# PCBRecSCH.net
KiCad netlist of a schematic drawn in Altium Designer
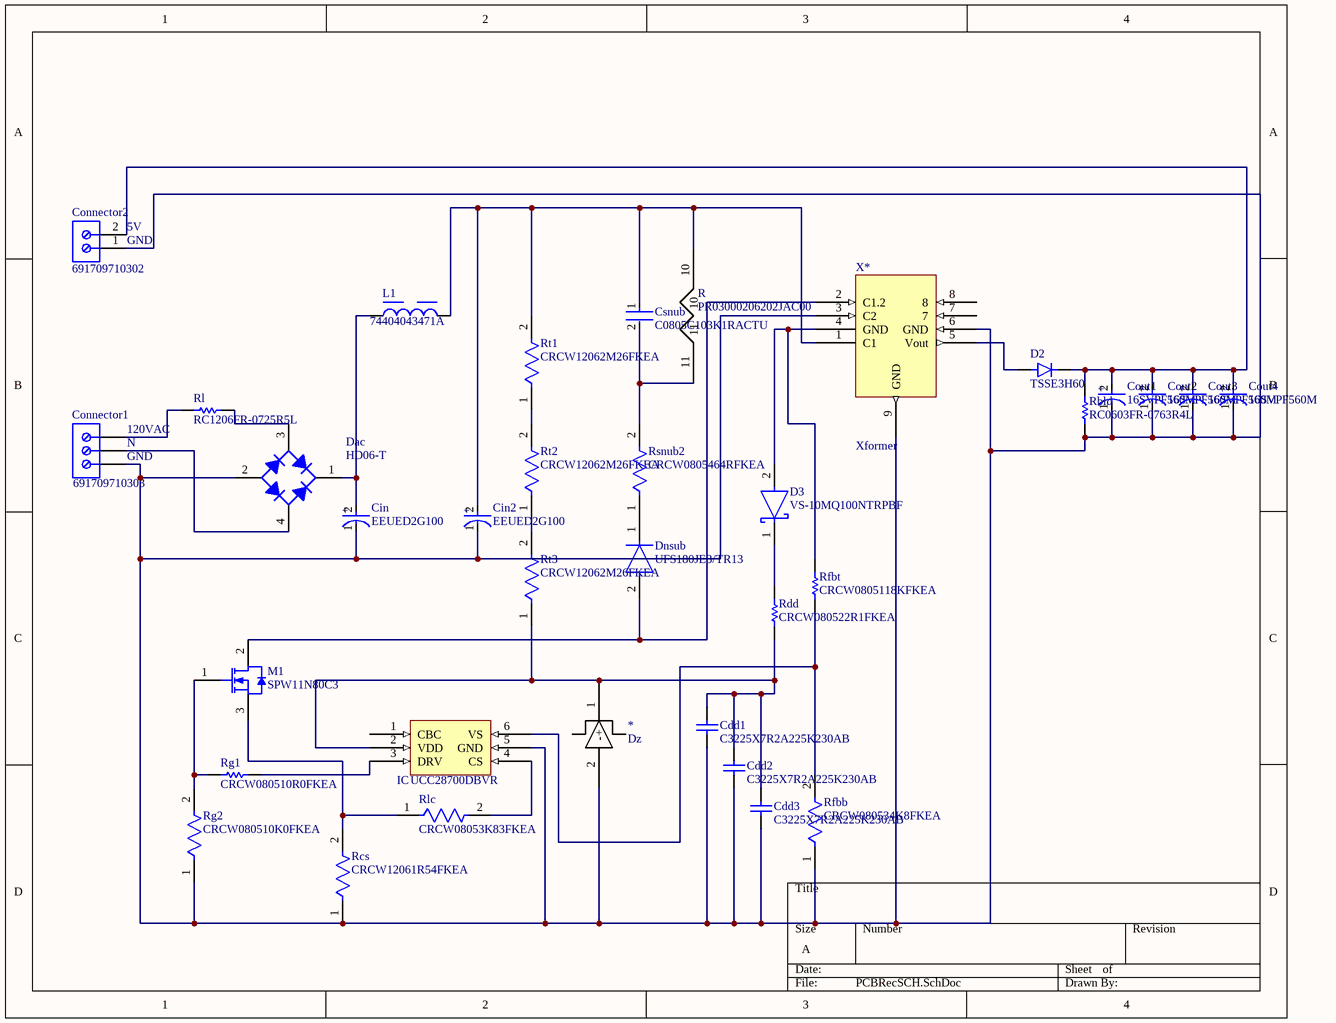
[diagram p0: PCBRecSCH.SchDoc]

(export (version "E")
  (design (tool "Eeschema 10.0.6"))
  (components
    (comp (ref "*")
      (value "Dz")
      (footprint "DIOM505270X240")
      (libsource (lib "Integrated_Library2") (part "Component_1"))
    )
    (comp (ref "Cdd1")
      (value "C3225X7R2A225K230AB")
      (footprint "CAPC3225X250X20LL40")
      (description "Chip Capacitor, 2.2 uF, +/- 10%, -55 to 125 degC, 1210 (3225 Metric), RoHS, Tape and Reel")
      (fields
        (field (name "PCN PART NUMBER") "MLCCPartNumberChange30/Nov/2012")
        (field (name "MANUFACTURER") "TDK")
      )
      (libsource (lib "Altium Content Vault") (part "CAP-NP-2"))
    )
    (comp (ref "Cdd2")
      (value "C3225X7R2A225K230AB")
      (footprint "CAPC3225X250X20LL40")
      (description "Chip Capacitor, 2.2 uF, +/- 10%, -55 to 125 degC, 1210 (3225 Metric), RoHS, Tape and Reel")
      (fields
        (field (name "PCN PART NUMBER") "MLCCPartNumberChange30/Nov/2012")
        (field (name "MANUFACTURER") "TDK")
      )
      (libsource (lib "Altium Content Vault") (part "CAP-NP-2"))
    )
    (comp (ref "Cdd3")
      (value "C3225X7R2A225K230AB")
      (footprint "CAPC3225X250X20LL40")
      (description "Chip Capacitor, 2.2 uF, +/- 10%, -55 to 125 degC, 1210 (3225 Metric), RoHS, Tape and Reel")
      (fields
        (field (name "PCN PART NUMBER") "MLCCPartNumberChange30/Nov/2012")
        (field (name "MANUFACTURER") "TDK")
      )
      (libsource (lib "Altium Content Vault") (part "CAP-NP-2"))
    )
    (comp (ref "Cin")
      (value "EEUED2G100")
      (footprint "FP-RAD-TH-D_10_0_5-L_20_2-MFG")
      (description "Aluminum Electrolytic Capacitors (Radial Lead Type) 10uF ±20% 400V")
      (fields (field (name "VOLTAGE") "400V") (field (name "TOLERANCE") "20%"))
      (libsource (lib "Altium Content Vault") (part "203bc49f2ac43e59fd269a8c329ed05"))
    )
    (comp (ref "Cin2")
      (value "EEUED2G100")
      (footprint "FP-RAD-TH-D_10_0_5-L_20_2-MFG")
      (description "Aluminum Electrolytic Capacitors (Radial Lead Type) 10uF ±20% 400V")
      (fields (field (name "VOLTAGE") "400V") (field (name "TOLERANCE") "20%"))
      (libsource (lib "Altium Content Vault") (part "203bc49f2ac43e59fd269a8c329ed05"))
    )
    (comp (ref "Connector1")
      (value "691709710303")
      (footprint "691709710303")
      (fields (field (name "VOLTAGE") "300V"))
      (libsource (lib "Altium Content Vault") (part "TBL - 1R - 03P - Screw"))
    )
    (comp (ref "Connector2")
      (value "691709710302")
      (footprint "691709710302")
      (fields (field (name "VOLTAGE") "300V"))
      (libsource (lib "Altium Content Vault") (part "TBL - 1R - 02P - Screw"))
    )
    (comp (ref "Cout1")
      (value "16SVPF560M")
      (footprint "FP-OS-CON-SMT-E12-MFG")
      (description "Conductive Polymer Aluminum Solid Capacitors (OS-CON) 560uF ±20% 16V")
      (fields (field (name "TOLERANCE") "20%") (field (name "VOLTAGE") "16V"))
      (libsource (lib "Altium Content Vault") (part "a00bbbee19879c290e62620ae7e47b1"))
    )
    (comp (ref "Cout2")
      (value "16SVPF560M")
      (footprint "FP-OS-CON-SMT-E12-MFG")
      (description "Conductive Polymer Aluminum Solid Capacitors (OS-CON) 560uF ±20% 16V")
      (fields (field (name "TOLERANCE") "20%") (field (name "VOLTAGE") "16V"))
      (libsource (lib "Altium Content Vault") (part "a00bbbee19879c290e62620ae7e47b1"))
    )
    (comp (ref "Cout3")
      (value "16SVPF560M")
      (footprint "FP-OS-CON-SMT-E12-MFG")
      (description "Conductive Polymer Aluminum Solid Capacitors (OS-CON) 560uF ±20% 16V")
      (fields (field (name "TOLERANCE") "20%") (field (name "VOLTAGE") "16V"))
      (libsource (lib "Altium Content Vault") (part "a00bbbee19879c290e62620ae7e47b1"))
    )
    (comp (ref "Cout4")
      (value "16SVPF560M")
      (footprint "FP-OS-CON-SMT-E12-MFG")
      (description "Conductive Polymer Aluminum Solid Capacitors (OS-CON) 560uF ±20% 16V")
      (fields (field (name "TOLERANCE") "20%") (field (name "VOLTAGE") "16V"))
      (libsource (lib "Altium Content Vault") (part "a00bbbee19879c290e62620ae7e47b1"))
    )
    (comp (ref "Csnub")
      (value "C0805C103K1RACTU")
      (footprint "FP-C0805C-DN-MFG")
      (description "CAP CER 10000PF 100V X7R 0805")
      (fields
        (field (name "OCTOPART") "https://octopart.com/c0805c103k1ractu-kemet-97824")
        (field (name "MANUFACTURER") "KEMET")
      )
      (libsource (lib "Altium Content Vault") (part "b4654b650e69147ec39a6b967a45e02"))
    )
    (comp (ref "D2")
      (value "TSSE3H60")
      (footprint "DIO_TSSE3H60")
      (fields (field (name "MF") "Taiwan Semiconductor"))
      (libsource (lib "TSSE3H60") (part "TSSE3H60"))
    )
    (comp (ref "D3")
      (value "VS-10MQ100NTRPBF")
      (footprint "FP-95400-MFG")
      (description "DIODE SCHOTTKY 100V 1A SMA")
      (fields
        (field (name "OCTOPART") "https://octopart.com/vs-10mq100ntrpbf-vishay-44340924")
        (field (name "MANUFACTURER") "Vishay")
      )
      (libsource (lib "Altium Content Vault") (part "c1678fac7984e62e0809fbf79c06691"))
    )
    (comp (ref "Dac")
      (value "HD06-T")
      (footprint "DIOD-MiniDIP-4_V")
      (fields (field (name "MANUFACTURER") "Diodes Inc"))
      (libsource (lib "Altium Content Vault") (part "D-KACC-4"))
    )
    (comp (ref "Dnsub")
      (value "UFS180JE3/TR13")
      (footprint "FP-DO-214BA-MFG")
      (description "UFS180JE3/TR13 Rectifier Diode, 1 Phase, 1 Element, 1A, 800V V(RRM)")
      (libsource (lib "Altium Content Vault") (part "d7152d700b627762746794eb795d46e"))
    )
    (comp (ref "IC")
      (value "UCC28700DBVR")
      (footprint "SOT95P280X145-6N")
      (libsource (lib "Integrated_Library1") (part "Component_2"))
    )
    (comp (ref "L1")
      (value "74404043471A")
      (footprint "WE-LQS_4025")
      (description "74404043471A Inductor, 470Uh, Semishielded, 0.25A Rohs Compliant: Yes")
      (libsource (lib "Altium Content Vault") (part "Inductor - 3"))
    )
    (comp (ref "M1")
      (value "SPW11N80C3")
      (footprint "INF-PG-TO247-3-21")
      (fields (field (name "MANUFACTURER") "Infineon"))
      (libsource (lib "Altium Content Vault") (part "INF-NEMOS-GDS-3"))
    )
    (comp (ref "R")
      (value "PR03000206202JAC00")
      (footprint "PCBComponent_1")
      (libsource (lib "Integrated_Library3") (part "Component_1"))
    )
    (comp (ref "Rbld")
      (value "RC0603FR-0763R4L")
      (footprint "RESC1608X55X25NL10T15")
      (fields (field (name "MANUFACTURER") "Yageo"))
      (libsource (lib "Altium Content Vault") (part "RES"))
    )
    (comp (ref "Rcs")
      (value "CRCW12061R54FKEA")
      (footprint "FP-CRCW1206-e3-MFG")
      (description "RES Thick Film, 1.54Ω, 1%, 0.25W, 100ppm/°C, 1206")
      (fields (field (name "TOLERANCE") "1%"))
      (libsource (lib "Altium Content Vault") (part "1029c3af85768c4190bb7ad29bc67b5"))
    )
    (comp (ref "Rdd")
      (value "CRCW080522R1FKEA")
      (footprint "RESC2013X50X30ML20T20")
      (fields (field (name "MANUFACTURER") "Vishay Dale"))
      (libsource (lib "Altium Content Vault") (part "RES"))
    )
    (comp (ref "Rfbb")
      (value "CRCW080534K8FKEA")
      (footprint "FP-CRCW0805-e3-IPC_C")
      (description "RES Thick Film, 34.8kΩ, 1%, 0.125W, 100ppm/°C, 0805")
      (fields (field (name "TOLERANCE") "1%"))
      (libsource (lib "Altium Content Vault") (part "1029c3af85768c4190bb7ad29bc67b5"))
    )
    (comp (ref "Rfbt")
      (value "CRCW0805118KFKEA")
      (footprint "RESC2013X50X30ML20T20")
      (fields (field (name "MANUFACTURER") "Vishay Dale"))
      (libsource (lib "Altium Content Vault") (part "RES"))
    )
    (comp (ref "Rg1")
      (value "CRCW080510R0FKEA")
      (footprint "RESC2013X50X30NL20T20")
      (fields (field (name "MANUFACTURER") "Vishay Dale"))
      (libsource (lib "Altium Content Vault") (part "RES"))
    )
    (comp (ref "Rg2")
      (value "CRCW080510K0FKEA")
      (footprint "FP-CRCW0805-e3-IPC_A")
      (description "RES Thick Film, 10kΩ, 1%, 0.125W, 100ppm/°C, 0805")
      (fields (field (name "TOLERANCE") "1%"))
      (libsource (lib "Altium Content Vault") (part "1029c3af85768c4190bb7ad29bc67b5"))
    )
    (comp (ref "Rl")
      (value "RC1206FR-0725R5L")
      (footprint "RESC3116X65X40NL10T20")
      (fields (field (name "MANUFACTURER") "Yageo"))
      (libsource (lib "Altium Content Vault") (part "RES"))
    )
    (comp (ref "Rlc")
      (value "CRCW08053K83FKEA")
      (footprint "FP-CRCW0805-e3-IPC_B")
      (description "RES Thick Film, 3.83kΩ, 1%, 0.125W, 100ppm/°C, 0805")
      (fields (field (name "TOLERANCE") "1%"))
      (libsource (lib "Altium Content Vault") (part "1029c3af85768c4190bb7ad29bc67b5"))
    )
    (comp (ref "Rsnub2")
      (value "CRCW0805464RFKEA")
      (footprint "FP-CRCW0805-e3-IPC_A")
      (description "RES Thick Film, 464Ω, 1%, 0.125W, 100ppm/°C, 0805")
      (fields (field (name "TOLERANCE") "1%"))
      (libsource (lib "Altium Content Vault") (part "1029c3af85768c4190bb7ad29bc67b5"))
    )
    (comp (ref "Rt1")
      (value "CRCW12062M26FKEA")
      (footprint "FP-CRCW1206-e3-MFG")
      (description "RES Thick Film, 2.26MΩ, 1%, 0.25W, 100ppm/°C, 1206")
      (fields (field (name "TOLERANCE") "1%"))
      (libsource (lib "Altium Content Vault") (part "1029c3af85768c4190bb7ad29bc67b5"))
    )
    (comp (ref "Rt2")
      (value "CRCW12062M26FKEA")
      (footprint "FP-CRCW1206-e3-MFG")
      (description "RES Thick Film, 2.26MΩ, 1%, 0.25W, 100ppm/°C, 1206")
      (fields (field (name "TOLERANCE") "1%"))
      (libsource (lib "Altium Content Vault") (part "1029c3af85768c4190bb7ad29bc67b5"))
    )
    (comp (ref "Rt3")
      (value "CRCW12062M26FKEA")
      (footprint "FP-CRCW1206-e3-MFG")
      (description "RES Thick Film, 2.26MΩ, 1%, 0.25W, 100ppm/°C, 1206")
      (fields (field (name "TOLERANCE") "1%"))
      (libsource (lib "Altium Content Vault") (part "1029c3af85768c4190bb7ad29bc67b5"))
    )
    (comp (ref "X*")
      (value "Xformer")
      (footprint "PCBComponent_1")
      (libsource (lib "Integrated_Library4") (part "Component_4"))
    )
  )
  (nets
    (net (code "1") (name "Net-(*-+)") (class "Default")
      (node (ref "*") (pin "1") (pinfunction "+_1") (pintype "passive"))
      (node (ref "Cdd1") (pin "2") (pinfunction "2_2") (pintype "passive"))
      (node (ref "Cdd2") (pin "2") (pinfunction "2_2") (pintype "passive"))
      (node (ref "Cdd3") (pin "2") (pinfunction "2_2") (pintype "passive"))
      (node (ref "IC") (pin "2") (pinfunction "VDD_2") (pintype "input"))
      (node (ref "Rdd") (pin "1") (pinfunction "1_1") (pintype "passive"))
      (node (ref "Rt3") (pin "1") (pinfunction "1_1") (pintype "passive"))
    )
    (net (code "2") (name "Net-(*--)") (class "Default")
      (node (ref "*") (pin "2") (pinfunction "-_2") (pintype "passive"))
      (node (ref "Cdd1") (pin "1") (pinfunction "1_1") (pintype "passive"))
      (node (ref "Cdd2") (pin "1") (pinfunction "1_1") (pintype "passive"))
      (node (ref "Cdd3") (pin "1") (pinfunction "1_1") (pintype "passive"))
      (node (ref "Cin") (pin "1") (pinfunction "C_1") (pintype "passive"))
      (node (ref "Cin2") (pin "1") (pinfunction "C_1") (pintype "passive"))
      (node (ref "Connector1") (pin "1") (pinfunction "1_1") (pintype "passive"))
      (node (ref "Connector2") (pin "1") (pinfunction "1_1") (pintype "passive"))
      (node (ref "Cout1") (pin "1") (pinfunction "C_1") (pintype "passive"))
      (node (ref "Cout2") (pin "1") (pinfunction "C_1") (pintype "passive"))
      (node (ref "Cout3") (pin "1") (pinfunction "C_1") (pintype "passive"))
      (node (ref "Cout4") (pin "1") (pinfunction "C_1") (pintype "passive"))
      (node (ref "Dac") (pin "2") (pinfunction "A_2") (pintype "passive"))
      (node (ref "IC") (pin "5") (pinfunction "GND_5") (pintype "input"))
      (node (ref "Rbld") (pin "1") (pinfunction "1_1") (pintype "passive"))
      (node (ref "Rcs") (pin "1") (pinfunction "1_1") (pintype "passive"))
      (node (ref "Rfbb") (pin "1") (pinfunction "1_1") (pintype "passive"))
      (node (ref "Rg2") (pin "1") (pinfunction "1_1") (pintype "passive"))
      (node (ref "X*") (pin "3") (pinfunction "C2_3") (pintype "input"))
      (node (ref "X*") (pin "6") (pinfunction "GND_6") (pintype "input"))
      (node (ref "X*") (pin "9") (pinfunction "GND_9") (pintype "output"))
    )
    (net (code "3") (name "Net-(Cin-A)") (class "Default")
      (node (ref "Cin") (pin "2") (pinfunction "A_2") (pintype "passive"))
      (node (ref "Dac") (pin "1") (pinfunction "K_1") (pintype "passive"))
      (node (ref "L1") (pin "1") (pinfunction "1_1") (pintype "passive"))
    )
    (net (code "4") (name "Net-(Cin2-A)") (class "Default")
      (node (ref "Cin2") (pin "2") (pinfunction "A_2") (pintype "passive"))
      (node (ref "Csnub") (pin "1") (pinfunction "1_1") (pintype "passive"))
      (node (ref "L1") (pin "2") (pinfunction "2_2") (pintype "passive"))
      (node (ref "R") (pin "10") (pinfunction "10_10") (pintype "passive"))
      (node (ref "Rt1") (pin "2") (pinfunction "2_2") (pintype "passive"))
      (node (ref "X*") (pin "1") (pinfunction "C1_1") (pintype "passive"))
    )
    (net (code "5") (name "Net-(Connector1-Pad2)") (class "Default")
      (node (ref "Connector1") (pin "2") (pinfunction "2_2") (pintype "passive"))
      (node (ref "Dac") (pin "4") (pinfunction "C_4") (pintype "passive"))
    )
    (net (code "6") (name "Net-(Connector1-Pad3)") (class "Default")
      (node (ref "Connector1") (pin "3") (pinfunction "3_3") (pintype "passive"))
      (node (ref "Rl") (pin "1") (pinfunction "1_1") (pintype "passive"))
    )
    (net (code "7") (name "Net-(Cout1-A)") (class "Default")
      (node (ref "Connector2") (pin "2") (pinfunction "2_2") (pintype "passive"))
      (node (ref "Cout1") (pin "2") (pinfunction "A_2") (pintype "passive"))
      (node (ref "Cout2") (pin "2") (pinfunction "A_2") (pintype "passive"))
      (node (ref "Cout3") (pin "2") (pinfunction "A_2") (pintype "passive"))
      (node (ref "Cout4") (pin "2") (pinfunction "A_2") (pintype "passive"))
      (node (ref "D2") (pin "C") (pinfunction "K_C") (pintype "passive"))
      (node (ref "Rbld") (pin "2") (pinfunction "2_2") (pintype "passive"))
    )
    (net (code "8") (name "Net-(Csnub-Pad2)") (class "Default")
      (node (ref "Csnub") (pin "2") (pinfunction "2_2") (pintype "passive"))
      (node (ref "R") (pin "11") (pinfunction "11_11") (pintype "passive"))
      (node (ref "Rsnub2") (pin "2") (pinfunction "2_2") (pintype "passive"))
    )
    (net (code "9") (name "Net-(D3-A)") (class "Default")
      (node (ref "D3") (pin "2") (pinfunction "A_2") (pintype "passive"))
      (node (ref "Rfbt") (pin "2") (pinfunction "2_2") (pintype "passive"))
      (node (ref "X*") (pin "4") (pinfunction "GND_4") (pintype "passive"))
    )
    (net (code "10") (name "Net-(D3-C)") (class "Default")
      (node (ref "D3") (pin "1") (pinfunction "C_1") (pintype "passive"))
      (node (ref "Rdd") (pin "2") (pinfunction "2_2") (pintype "passive"))
    )
    (net (code "11") (name "Net-(Dac-C-Pad3)") (class "Default")
      (node (ref "Dac") (pin "3") (pinfunction "C_3") (pintype "passive"))
      (node (ref "Rl") (pin "2") (pinfunction "2_2") (pintype "passive"))
    )
    (net (code "12") (name "Net-(Dnsub-A)") (class "Default")
      (node (ref "Dnsub") (pin "2") (pinfunction "A_2") (pintype "passive"))
      (node (ref "M1") (pin "2") (pinfunction "DRAIN_2") (pintype "passive"))
      (node (ref "X*") (pin "2") (pinfunction "C1.2_2") (pintype "input"))
    )
    (net (code "13") (name "Net-(Dnsub-C)") (class "Default")
      (node (ref "Dnsub") (pin "1") (pinfunction "C_1") (pintype "passive"))
      (node (ref "Rsnub2") (pin "1") (pinfunction "1_1") (pintype "passive"))
    )
    (net (code "14") (name "Net-(IC-CS)") (class "Default")
      (node (ref "IC") (pin "4") (pinfunction "CS_4") (pintype "input"))
      (node (ref "Rlc") (pin "2") (pinfunction "2_2") (pintype "passive"))
    )
    (net (code "15") (name "Net-(IC-DRV)") (class "Default")
      (node (ref "IC") (pin "3") (pinfunction "DRV_3") (pintype "input"))
      (node (ref "Rg1") (pin "2") (pinfunction "2_2") (pintype "passive"))
    )
    (net (code "16") (name "Net-(IC-VS)") (class "Default")
      (node (ref "IC") (pin "6") (pinfunction "VS_6") (pintype "input"))
      (node (ref "Rfbb") (pin "2") (pinfunction "2_2") (pintype "passive"))
      (node (ref "Rfbt") (pin "1") (pinfunction "1_1") (pintype "passive"))
    )
    (net (code "17") (name "Net-(M1-GATE)") (class "Default")
      (node (ref "M1") (pin "1") (pinfunction "GATE_1") (pintype "passive"))
      (node (ref "Rg1") (pin "1") (pinfunction "1_1") (pintype "passive"))
      (node (ref "Rg2") (pin "2") (pinfunction "2_2") (pintype "passive"))
    )
    (net (code "18") (name "Net-(M1-SOURCE)") (class "Default")
      (node (ref "M1") (pin "3") (pinfunction "SOURCE_3") (pintype "passive"))
      (node (ref "Rcs") (pin "2") (pinfunction "2_2") (pintype "passive"))
      (node (ref "Rlc") (pin "1") (pinfunction "1_1") (pintype "passive"))
    )
    (net (code "19") (name "Net-(Rt1-Pad1)") (class "Default")
      (node (ref "Rt1") (pin "1") (pinfunction "1_1") (pintype "passive"))
      (node (ref "Rt2") (pin "2") (pinfunction "2_2") (pintype "passive"))
    )
    (net (code "20") (name "Net-(Rt2-Pad1)") (class "Default")
      (node (ref "Rt2") (pin "1") (pinfunction "1_1") (pintype "passive"))
      (node (ref "Rt3") (pin "2") (pinfunction "2_2") (pintype "passive"))
    )
    (net (code "21") (name "Net-(X*-Vout)") (class "Default")
      (node (ref "D2") (pin "A") (pinfunction "A_A") (pintype "passive"))
      (node (ref "X*") (pin "5") (pinfunction "Vout_5") (pintype "output"))
    )
    (net (code "22") (name "unconnected-(IC-CBC-Pad1)") (class "Default")
      (node (ref "IC") (pin "1") (pinfunction "CBC_1") (pintype "input"))
    )
    (net (code "23") (name "unconnected-(X*-Pad7)") (class "Default")
      (node (ref "X*") (pin "7") (pinfunction "7_7") (pintype "input"))
    )
    (net (code "24") (name "unconnected-(X*-Pad8)") (class "Default")
      (node (ref "X*") (pin "8") (pinfunction "8_8") (pintype "input"))
    )
  )
)
